# relay_pro.net
KiCad netlist of a schematic drawn in EAGLE
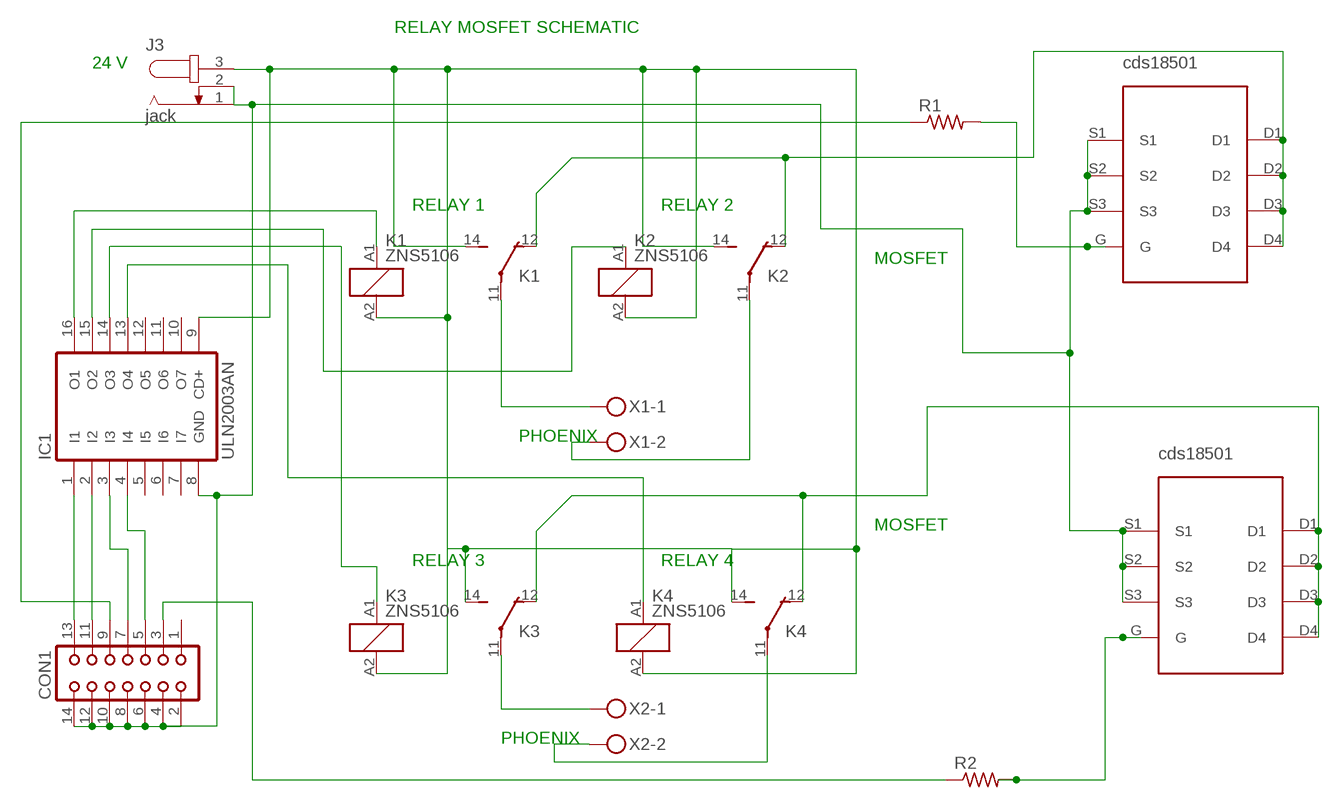
[diagram p0: schematic, sheet 1]

(export (version "E")
  (design (tool "Eeschema 10.0.6"))
  (components
    (comp (ref "CON1")
      (value "CON14")
      (footprint "eagle-import:CON14")
      (libsource (lib "eagle-import") (part "CON14"))
    )
    (comp (ref "IC1")
      (value "ULN2003AN")
      (footprint "eagle-import:DIL16")
      (libsource (lib "eagle-import") (part "ULN2003AN"))
    )
    (comp (ref "J3")
      (value "jack")
      (footprint "eagle-import:SPC4077")
      (libsource (lib "eagle-import") (part "JACK-PLUG0"))
    )
    (comp (ref "K1")
      (value "ZNS5106")
      (footprint "eagle-import:ZN5")
      (libsource (lib "eagle-import") (part "ZNS5106"))
    )
    (comp (ref "K2")
      (value "ZNS5106")
      (footprint "eagle-import:ZN5")
      (libsource (lib "eagle-import") (part "ZNS5106"))
    )
    (comp (ref "K3")
      (value "ZNS5106")
      (footprint "eagle-import:ZN5")
      (libsource (lib "eagle-import") (part "ZNS5106"))
    )
    (comp (ref "K4")
      (value "ZNS5106")
      (footprint "eagle-import:ZN5")
      (libsource (lib "eagle-import") (part "ZNS5106"))
    )
    (comp (ref "R1")
      (value "R-US_R0603")
      (footprint "eagle-import:R0603")
      (libsource (lib "eagle-import") (part "R-US_R0603"))
    )
    (comp (ref "R2")
      (value "R-US_R0603")
      (footprint "eagle-import:R0603")
      (libsource (lib "eagle-import") (part "R-US_R0603"))
    )
    (comp (ref "U$1")
      (value "CSD18503GDS-NEW")
      (footprint "eagle-import:CDS")
      (libsource (lib "eagle-import") (part "CSD18503GDS-NEW"))
    )
    (comp (ref "U$2")
      (value "CSD18503GDS-NEW")
      (footprint "eagle-import:CDS")
      (libsource (lib "eagle-import") (part "CSD18503GDS-NEW"))
    )
    (comp (ref "X1")
      (value "MKDSN1,5/2-5,08")
      (footprint "eagle-import:MKDSN1,5_2-5,08")
      (libsource (lib "eagle-import") (part "MKDSN1,5/2-5,08"))
    )
    (comp (ref "X2")
      (value "MKDSN1,5/2-5,08")
      (footprint "eagle-import:MKDSN1,5_2-5,08")
      (libsource (lib "eagle-import") (part "MKDSN1,5/2-5,08"))
    )
  )
  (nets
    (net (code "1") (name "Net-(CON1-Pad3)") (class "Default")
      (node (ref "CON1") (pin "3") (pinfunction "3_3") (pintype "passive"))
      (node (ref "R2") (pin "1") (pinfunction "1_1") (pintype "passive"))
    )
    (net (code "2") (name "Net-(CON1-Pad9)") (class "Default")
      (node (ref "CON1") (pin "9") (pinfunction "9_9") (pintype "passive"))
      (node (ref "R1") (pin "1") (pinfunction "1_1") (pintype "passive"))
    )
    (net (code "3") (name "Net-(IC1-CD+)") (class "Default")
      (node (ref "IC1") (pin "9") (pinfunction "CD+_9") (pintype "passive"))
      (node (ref "J3") (pin "3") (pinfunction "3_3") (pintype "passive"))
      (node (ref "K1") (pin "14") (pinfunction "S_14") (pintype "passive"))
      (node (ref "K1") (pin "A2") (pinfunction "2_A2") (pintype "passive"))
      (node (ref "K2") (pin "14") (pinfunction "S_14") (pintype "passive"))
      (node (ref "K2") (pin "A2") (pinfunction "2_A2") (pintype "passive"))
      (node (ref "K3") (pin "14") (pinfunction "S_14") (pintype "passive"))
      (node (ref "K3") (pin "A2") (pinfunction "2_A2") (pintype "passive"))
      (node (ref "K4") (pin "14") (pinfunction "S_14") (pintype "passive"))
      (node (ref "K4") (pin "A2") (pinfunction "2_A2") (pintype "passive"))
    )
    (net (code "4") (name "Net-(IC1-GND)") (class "Default")
      (node (ref "CON1") (pin "10") (pinfunction "10_10") (pintype "passive"))
      (node (ref "CON1") (pin "12") (pinfunction "12_12") (pintype "passive"))
      (node (ref "CON1") (pin "14") (pinfunction "14_14") (pintype "passive"))
      (node (ref "CON1") (pin "2") (pinfunction "2_2") (pintype "passive"))
      (node (ref "CON1") (pin "4") (pinfunction "4_4") (pintype "passive"))
      (node (ref "CON1") (pin "6") (pinfunction "6_6") (pintype "passive"))
      (node (ref "CON1") (pin "8") (pinfunction "8_8") (pintype "passive"))
      (node (ref "IC1") (pin "8") (pinfunction "GND_8") (pintype "power_in"))
      (node (ref "J3") (pin "1") (pinfunction "1_1") (pintype "passive"))
      (node (ref "J3") (pin "2") (pinfunction "2_2") (pintype "passive"))
      (node (ref "U$1") (pin "S1") (pinfunction "S1_S1") (pintype "bidirectional"))
      (node (ref "U$1") (pin "S2") (pinfunction "S2_S2") (pintype "bidirectional"))
      (node (ref "U$1") (pin "S3") (pinfunction "S3_S3") (pintype "bidirectional"))
      (node (ref "U$2") (pin "S1") (pinfunction "S1_S1") (pintype "bidirectional"))
      (node (ref "U$2") (pin "S2") (pinfunction "S2_S2") (pintype "bidirectional"))
      (node (ref "U$2") (pin "S3") (pinfunction "S3_S3") (pintype "bidirectional"))
    )
    (net (code "5") (name "Net-(IC1-I1)") (class "Default")
      (node (ref "CON1") (pin "13") (pinfunction "13_13") (pintype "passive"))
      (node (ref "IC1") (pin "1") (pinfunction "I1_1") (pintype "input"))
    )
    (net (code "6") (name "Net-(IC1-I2)") (class "Default")
      (node (ref "CON1") (pin "11") (pinfunction "11_11") (pintype "passive"))
      (node (ref "IC1") (pin "2") (pinfunction "I2_2") (pintype "input"))
    )
    (net (code "7") (name "Net-(IC1-I3)") (class "Default")
      (node (ref "CON1") (pin "7") (pinfunction "7_7") (pintype "passive"))
      (node (ref "IC1") (pin "3") (pinfunction "I3_3") (pintype "input"))
    )
    (net (code "8") (name "Net-(IC1-I4)") (class "Default")
      (node (ref "CON1") (pin "5") (pinfunction "5_5") (pintype "passive"))
      (node (ref "IC1") (pin "4") (pinfunction "I4_4") (pintype "input"))
    )
    (net (code "9") (name "Net-(IC1-O1)") (class "Default")
      (node (ref "IC1") (pin "16") (pinfunction "O1_16") (pintype "open_collector"))
      (node (ref "K1") (pin "A1") (pinfunction "1_A1") (pintype "passive"))
    )
    (net (code "10") (name "Net-(IC1-O2)") (class "Default")
      (node (ref "IC1") (pin "15") (pinfunction "O2_15") (pintype "open_collector"))
      (node (ref "K2") (pin "A1") (pinfunction "1_A1") (pintype "passive"))
    )
    (net (code "11") (name "Net-(IC1-O3)") (class "Default")
      (node (ref "IC1") (pin "14") (pinfunction "O3_14") (pintype "open_collector"))
      (node (ref "K3") (pin "A1") (pinfunction "1_A1") (pintype "passive"))
    )
    (net (code "12") (name "Net-(IC1-O4)") (class "Default")
      (node (ref "IC1") (pin "13") (pinfunction "O4_13") (pintype "open_collector"))
      (node (ref "K4") (pin "A1") (pinfunction "1_A1") (pintype "passive"))
    )
    (net (code "13") (name "Net-(K1B-O)") (class "Default")
      (node (ref "K1") (pin "12") (pinfunction "O_12") (pintype "passive"))
      (node (ref "K2") (pin "12") (pinfunction "O_12") (pintype "passive"))
      (node (ref "U$1") (pin "D1") (pinfunction "D1_D1") (pintype "bidirectional"))
      (node (ref "U$1") (pin "D2") (pinfunction "D2_D2") (pintype "bidirectional"))
      (node (ref "U$1") (pin "D3") (pinfunction "D3_D3") (pintype "bidirectional"))
      (node (ref "U$1") (pin "D4") (pinfunction "D4_D4") (pintype "bidirectional"))
    )
    (net (code "14") (name "Net-(K1B-P)") (class "Default")
      (node (ref "K1") (pin "11") (pinfunction "P_11") (pintype "passive"))
      (node (ref "X1") (pin "1") (pinfunction "KL_1") (pintype "passive"))
    )
    (net (code "15") (name "Net-(K2B-P)") (class "Default")
      (node (ref "K2") (pin "11") (pinfunction "P_11") (pintype "passive"))
      (node (ref "X1") (pin "2") (pinfunction "KL_2") (pintype "passive"))
    )
    (net (code "16") (name "Net-(K3B-O)") (class "Default")
      (node (ref "K3") (pin "12") (pinfunction "O_12") (pintype "passive"))
      (node (ref "K4") (pin "12") (pinfunction "O_12") (pintype "passive"))
      (node (ref "U$2") (pin "D1") (pinfunction "D1_D1") (pintype "bidirectional"))
      (node (ref "U$2") (pin "D2") (pinfunction "D2_D2") (pintype "bidirectional"))
      (node (ref "U$2") (pin "D3") (pinfunction "D3_D3") (pintype "bidirectional"))
      (node (ref "U$2") (pin "D4") (pinfunction "D4_D4") (pintype "bidirectional"))
    )
    (net (code "17") (name "Net-(K3B-P)") (class "Default")
      (node (ref "K3") (pin "11") (pinfunction "P_11") (pintype "passive"))
      (node (ref "X2") (pin "1") (pinfunction "KL_1") (pintype "passive"))
    )
    (net (code "18") (name "Net-(K4B-P)") (class "Default")
      (node (ref "K4") (pin "11") (pinfunction "P_11") (pintype "passive"))
      (node (ref "X2") (pin "2") (pinfunction "KL_2") (pintype "passive"))
    )
    (net (code "19") (name "Net-(R1-Pad2)") (class "Default")
      (node (ref "R1") (pin "2") (pinfunction "2_2") (pintype "passive"))
      (node (ref "U$1") (pin "G") (pinfunction "G_G") (pintype "bidirectional"))
    )
    (net (code "20") (name "Net-(R2-Pad2)") (class "Default")
      (node (ref "R2") (pin "2") (pinfunction "2_2") (pintype "passive"))
      (node (ref "U$2") (pin "G") (pinfunction "G_G") (pintype "bidirectional"))
    )
    (net (code "21") (name "unconnected-(CON1-Pad1)") (class "Default")
      (node (ref "CON1") (pin "1") (pinfunction "1_1") (pintype "passive"))
    )
    (net (code "22") (name "unconnected-(IC1-I5-Pad5)") (class "Default")
      (node (ref "IC1") (pin "5") (pinfunction "I5_5") (pintype "input"))
    )
    (net (code "23") (name "unconnected-(IC1-I6-Pad6)") (class "Default")
      (node (ref "IC1") (pin "6") (pinfunction "I6_6") (pintype "input"))
    )
    (net (code "24") (name "unconnected-(IC1-I7-Pad7)") (class "Default")
      (node (ref "IC1") (pin "7") (pinfunction "I7_7") (pintype "input"))
    )
    (net (code "25") (name "unconnected-(IC1-O5-Pad12)") (class "Default")
      (node (ref "IC1") (pin "12") (pinfunction "O5_12") (pintype "open_collector"))
    )
    (net (code "26") (name "unconnected-(IC1-O6-Pad11)") (class "Default")
      (node (ref "IC1") (pin "11") (pinfunction "O6_11") (pintype "open_collector"))
    )
    (net (code "27") (name "unconnected-(IC1-O7-Pad10)") (class "Default")
      (node (ref "IC1") (pin "10") (pinfunction "O7_10") (pintype "open_collector"))
    )
  )
)
